# satshakit_fc_power.net
KiCad netlist of a schematic drawn in EAGLE
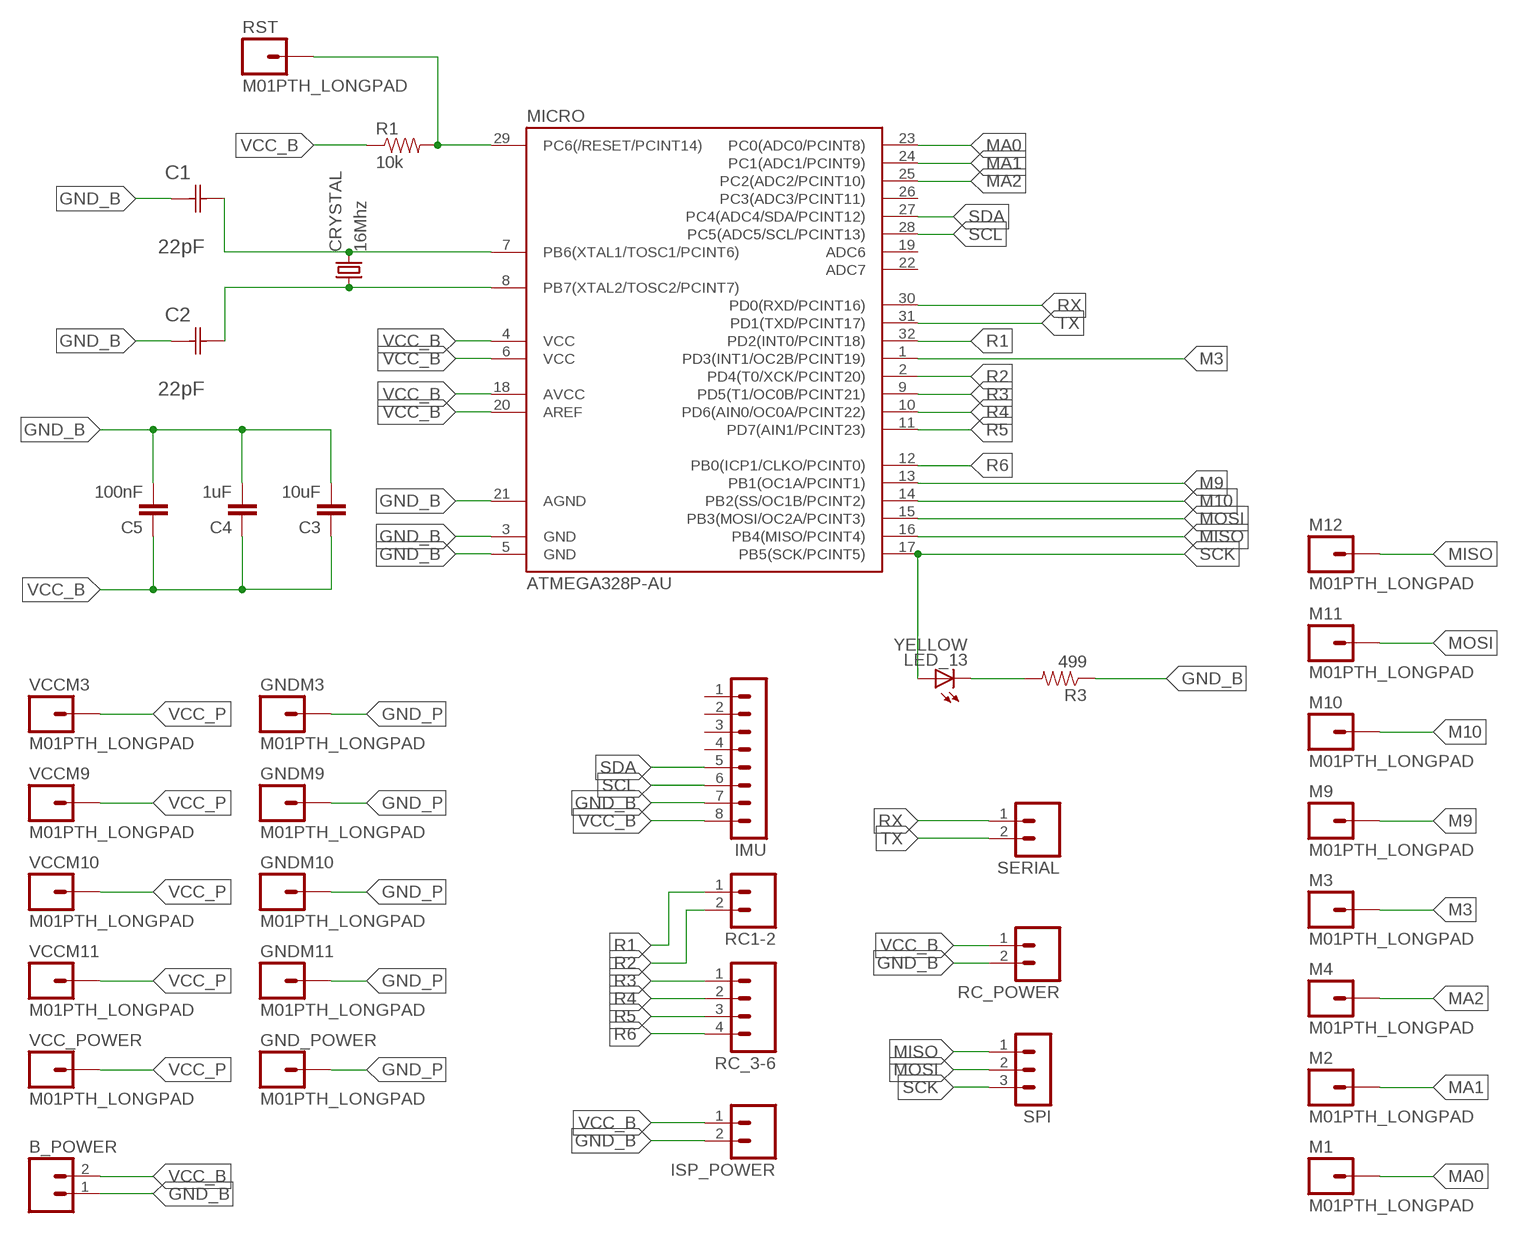
[diagram p0: schematic, sheet 1]

(export (version "E")
  (design (tool "Eeschema 10.0.6"))
  (components
    (comp (ref "B_POWER")
      (value "M02LOCK_LONGPADS")
      (footprint "eagle-import:1X02_LOCK_LONGPADS")
      (libsource (lib "eagle-import") (part "M02LOCK_LONGPADS"))
    )
    (comp (ref "C1")
      (value "22pF")
      (footprint "eagle-import:CAPC3216X178N")
      (fields (field (name "MPN") "0612ZC225MAT2A") (field (name "TOLERANCE") "±20%"))
      (libsource (lib "eagle-import") (part "0612ZC225MAT2A"))
    )
    (comp (ref "C2")
      (value "22pF")
      (footprint "eagle-import:CAPC3216X178N")
      (fields (field (name "MPN") "0612ZC225MAT2A") (field (name "TOLERANCE") "±20%"))
      (libsource (lib "eagle-import") (part "0612ZC225MAT2A"))
    )
    (comp (ref "C3")
      (value "10uF")
      (footprint "eagle-import:1206")
      (libsource (lib "eagle-import") (part "CAP1206"))
    )
    (comp (ref "C4")
      (value "1uF")
      (footprint "eagle-import:1206")
      (libsource (lib "eagle-import") (part "CAP1206"))
    )
    (comp (ref "C5")
      (value "100nF")
      (footprint "eagle-import:1206")
      (libsource (lib "eagle-import") (part "CAP1206"))
    )
    (comp (ref "CRYSTAL")
      (value "16Mhz")
      (footprint "eagle-import:CSM-7X-DU")
      (libsource (lib "eagle-import") (part "CSM-7X-DU"))
    )
    (comp (ref "GNDM3")
      (value "M01PTH_LONGPAD")
      (footprint "eagle-import:1X01_LONGPAD")
      (libsource (lib "eagle-import") (part "M01PTH_LONGPAD"))
    )
    (comp (ref "GNDM9")
      (value "M01PTH_LONGPAD")
      (footprint "eagle-import:1X01_LONGPAD")
      (libsource (lib "eagle-import") (part "M01PTH_LONGPAD"))
    )
    (comp (ref "GNDM10")
      (value "M01PTH_LONGPAD")
      (footprint "eagle-import:1X01_LONGPAD")
      (libsource (lib "eagle-import") (part "M01PTH_LONGPAD"))
    )
    (comp (ref "GNDM11")
      (value "M01PTH_LONGPAD")
      (footprint "eagle-import:1X01_LONGPAD")
      (libsource (lib "eagle-import") (part "M01PTH_LONGPAD"))
    )
    (comp (ref "GND_POWER")
      (value "M01PTH_LONGPAD")
      (footprint "eagle-import:1X01_LONGPAD")
      (libsource (lib "eagle-import") (part "M01PTH_LONGPAD"))
    )
    (comp (ref "IMU")
      (value "MA08-1")
      (footprint "eagle-import:MA08-1")
      (libsource (lib "eagle-import") (part "MA08-1"))
    )
    (comp (ref "ISP_POWER")
      (value "M02LOCK_LONGPADS")
      (footprint "eagle-import:1X02_LOCK_LONGPADS")
      (libsource (lib "eagle-import") (part "M02LOCK_LONGPADS"))
    )
    (comp (ref "LED_13")
      (value "YELLOW")
      (footprint "eagle-import:1206")
      (libsource (lib "eagle-import") (part "LED1206"))
    )
    (comp (ref "M1")
      (value "M01PTH_LONGPAD")
      (footprint "eagle-import:1X01_LONGPAD")
      (libsource (lib "eagle-import") (part "M01PTH_LONGPAD"))
    )
    (comp (ref "M2")
      (value "M01PTH_LONGPAD")
      (footprint "eagle-import:1X01_LONGPAD")
      (libsource (lib "eagle-import") (part "M01PTH_LONGPAD"))
    )
    (comp (ref "M3")
      (value "M01PTH_LONGPAD")
      (footprint "eagle-import:1X01_LONGPAD")
      (libsource (lib "eagle-import") (part "M01PTH_LONGPAD"))
    )
    (comp (ref "M4")
      (value "M01PTH_LONGPAD")
      (footprint "eagle-import:1X01_LONGPAD")
      (libsource (lib "eagle-import") (part "M01PTH_LONGPAD"))
    )
    (comp (ref "M9")
      (value "M01PTH_LONGPAD")
      (footprint "eagle-import:1X01_LONGPAD")
      (libsource (lib "eagle-import") (part "M01PTH_LONGPAD"))
    )
    (comp (ref "M10")
      (value "M01PTH_LONGPAD")
      (footprint "eagle-import:1X01_LONGPAD")
      (libsource (lib "eagle-import") (part "M01PTH_LONGPAD"))
    )
    (comp (ref "M11")
      (value "M01PTH_LONGPAD")
      (footprint "eagle-import:1X01_LONGPAD")
      (libsource (lib "eagle-import") (part "M01PTH_LONGPAD"))
    )
    (comp (ref "M12")
      (value "M01PTH_LONGPAD")
      (footprint "eagle-import:1X01_LONGPAD")
      (libsource (lib "eagle-import") (part "M01PTH_LONGPAD"))
    )
    (comp (ref "MICRO")
      (value "ATMEGA328P-AU")
      (footprint "eagle-import:TQFP32-08")
      (libsource (lib "eagle-import") (part "ATMEGA48/88/168-AU"))
    )
    (comp (ref "R1")
      (value "10k")
      (footprint "eagle-import:1206")
      (libsource (lib "eagle-import") (part "RESISTOR1206"))
    )
    (comp (ref "R3")
      (value "499")
      (footprint "eagle-import:1206")
      (libsource (lib "eagle-import") (part "RESISTOR1206"))
    )
    (comp (ref "RC1-2")
      (value "M02")
      (footprint "eagle-import:02P")
      (libsource (lib "eagle-import") (part "con-amp-quick_M02"))
    )
    (comp (ref "RC_3-6")
      (value "M04LONGPADS")
      (footprint "eagle-import:1X04_LONGPADS")
      (libsource (lib "eagle-import") (part "M04LONGPADS"))
    )
    (comp (ref "RC_POWER")
      (value "M02LOCK_LONGPADS")
      (footprint "eagle-import:1X02_LOCK_LONGPADS")
      (libsource (lib "eagle-import") (part "M02LOCK_LONGPADS"))
    )
    (comp (ref "RST")
      (value "M01PTH_LONGPAD")
      (footprint "eagle-import:1X01_LONGPAD")
      (libsource (lib "eagle-import") (part "M01PTH_LONGPAD"))
    )
    (comp (ref "SERIAL")
      (value "M02LOCK_LONGPADS")
      (footprint "eagle-import:1X02_LOCK_LONGPADS")
      (libsource (lib "eagle-import") (part "M02LOCK_LONGPADS"))
    )
    (comp (ref "SPI")
      (value "MA03-1")
      (footprint "eagle-import:MA03-1")
      (libsource (lib "eagle-import") (part "MA03-1"))
    )
    (comp (ref "VCCM3")
      (value "M01PTH_LONGPAD")
      (footprint "eagle-import:1X01_LONGPAD")
      (libsource (lib "eagle-import") (part "M01PTH_LONGPAD"))
    )
    (comp (ref "VCCM9")
      (value "M01PTH_LONGPAD")
      (footprint "eagle-import:1X01_LONGPAD")
      (libsource (lib "eagle-import") (part "M01PTH_LONGPAD"))
    )
    (comp (ref "VCCM10")
      (value "M01PTH_LONGPAD")
      (footprint "eagle-import:1X01_LONGPAD")
      (libsource (lib "eagle-import") (part "M01PTH_LONGPAD"))
    )
    (comp (ref "VCCM11")
      (value "M01PTH_LONGPAD")
      (footprint "eagle-import:1X01_LONGPAD")
      (libsource (lib "eagle-import") (part "M01PTH_LONGPAD"))
    )
    (comp (ref "VCC_POWER")
      (value "M01PTH_LONGPAD")
      (footprint "eagle-import:1X01_LONGPAD")
      (libsource (lib "eagle-import") (part "M01PTH_LONGPAD"))
    )
  )
  (nets
    (net (code "1") (name "GND_B") (class "Default")
      (node (ref "B_POWER") (pin "1") (pinfunction "1_1") (pintype "passive"))
      (node (ref "C1") (pin "1") (pinfunction "C1_1") (pintype "passive"))
      (node (ref "C2") (pin "1") (pinfunction "C1_1") (pintype "passive"))
      (node (ref "C3") (pin "2") (pinfunction "2_2") (pintype "passive"))
      (node (ref "C4") (pin "2") (pinfunction "2_2") (pintype "passive"))
      (node (ref "C5") (pin "2") (pinfunction "2_2") (pintype "passive"))
      (node (ref "IMU") (pin "7") (pinfunction "7_7") (pintype "passive"))
      (node (ref "ISP_POWER") (pin "2") (pinfunction "2_2") (pintype "passive"))
      (node (ref "MICRO") (pin "21") (pinfunction "AGND_21") (pintype "power_in"))
      (node (ref "MICRO") (pin "3") (pinfunction "GND_3") (pintype "power_in"))
      (node (ref "MICRO") (pin "5") (pinfunction "GND_5") (pintype "power_in"))
      (node (ref "R3") (pin "1") (pinfunction "1_1") (pintype "passive"))
      (node (ref "RC_POWER") (pin "2") (pinfunction "2_2") (pintype "passive"))
    )
    (net (code "2") (name "GND_P") (class "Default")
      (node (ref "GNDM10") (pin "1") (pinfunction "1_1") (pintype "passive"))
      (node (ref "GNDM11") (pin "1") (pinfunction "1_1") (pintype "passive"))
      (node (ref "GNDM3") (pin "1") (pinfunction "1_1") (pintype "passive"))
      (node (ref "GNDM9") (pin "1") (pinfunction "1_1") (pintype "passive"))
      (node (ref "GND_POWER") (pin "1") (pinfunction "1_1") (pintype "passive"))
    )
    (net (code "3") (name "M3") (class "Default")
      (node (ref "M3") (pin "1") (pinfunction "1_1") (pintype "passive"))
      (node (ref "MICRO") (pin "1") (pinfunction "PD3(INT1/OC2B/PCINT19)_1") (pintype "bidirectional"))
    )
    (net (code "4") (name "M9") (class "Default")
      (node (ref "M9") (pin "1") (pinfunction "1_1") (pintype "passive"))
      (node (ref "MICRO") (pin "13") (pinfunction "PB1(OC1A/PCINT1)_13") (pintype "bidirectional"))
    )
    (net (code "5") (name "M10") (class "Default")
      (node (ref "M10") (pin "1") (pinfunction "1_1") (pintype "passive"))
      (node (ref "MICRO") (pin "14") (pinfunction "PB2(SS/OC1B/PCINT2)_14") (pintype "bidirectional"))
    )
    (net (code "6") (name "MA0") (class "Default")
      (node (ref "M1") (pin "1") (pinfunction "1_1") (pintype "passive"))
      (node (ref "MICRO") (pin "23") (pinfunction "PC0(ADC0/PCINT8)_23") (pintype "bidirectional"))
    )
    (net (code "7") (name "MA1") (class "Default")
      (node (ref "M2") (pin "1") (pinfunction "1_1") (pintype "passive"))
      (node (ref "MICRO") (pin "24") (pinfunction "PC1(ADC1/PCINT9)_24") (pintype "bidirectional"))
    )
    (net (code "8") (name "MA2") (class "Default")
      (node (ref "M4") (pin "1") (pinfunction "1_1") (pintype "passive"))
      (node (ref "MICRO") (pin "25") (pinfunction "PC2(ADC2/PCINT10)_25") (pintype "bidirectional"))
    )
    (net (code "9") (name "MISO") (class "Default")
      (node (ref "M12") (pin "1") (pinfunction "1_1") (pintype "passive"))
      (node (ref "MICRO") (pin "16") (pinfunction "PB4(MISO/PCINT4)_16") (pintype "bidirectional"))
      (node (ref "SPI") (pin "1") (pinfunction "1_1") (pintype "passive"))
    )
    (net (code "10") (name "MOSI") (class "Default")
      (node (ref "M11") (pin "1") (pinfunction "1_1") (pintype "passive"))
      (node (ref "MICRO") (pin "15") (pinfunction "PB3(MOSI/OC2A/PCINT3)_15") (pintype "bidirectional"))
      (node (ref "SPI") (pin "2") (pinfunction "2_2") (pintype "passive"))
    )
    (net (code "11") (name "Net-(C1-C2)") (class "Default")
      (node (ref "C1") (pin "2") (pinfunction "C2_2") (pintype "passive"))
      (node (ref "CRYSTAL") (pin "2") (pinfunction "2_2") (pintype "passive"))
      (node (ref "MICRO") (pin "7") (pinfunction "PB6(XTAL1/TOSC1/PCINT6)_7") (pintype "bidirectional"))
    )
    (net (code "12") (name "Net-(C2-C2)") (class "Default")
      (node (ref "C2") (pin "2") (pinfunction "C2_2") (pintype "passive"))
      (node (ref "CRYSTAL") (pin "1") (pinfunction "1_1") (pintype "passive"))
      (node (ref "MICRO") (pin "8") (pinfunction "PB7(XTAL2/TOSC2/PCINT7)_8") (pintype "bidirectional"))
    )
    (net (code "13") (name "Net-(LED_13-C)") (class "Default")
      (node (ref "LED_13") (pin "2") (pinfunction "C_2") (pintype "passive"))
      (node (ref "R3") (pin "2") (pinfunction "2_2") (pintype "passive"))
    )
    (net (code "14") (name "Net-(MICRO-PC6({slash}RESET{slash}PCINT14))") (class "Default")
      (node (ref "MICRO") (pin "29") (pinfunction "PC6(/RESET/PCINT14)_29") (pintype "bidirectional"))
      (node (ref "R1") (pin "2") (pinfunction "2_2") (pintype "passive"))
      (node (ref "RST") (pin "1") (pinfunction "1_1") (pintype "passive"))
    )
    (net (code "15") (name "R1") (class "Default")
      (node (ref "MICRO") (pin "32") (pinfunction "PD2(INT0/PCINT18)_32") (pintype "bidirectional"))
      (node (ref "RC1-2") (pin "1") (pinfunction "1_1") (pintype "passive"))
    )
    (net (code "16") (name "R2") (class "Default")
      (node (ref "MICRO") (pin "2") (pinfunction "PD4(T0/XCK/PCINT20)_2") (pintype "bidirectional"))
      (node (ref "RC1-2") (pin "2") (pinfunction "2_2") (pintype "passive"))
    )
    (net (code "17") (name "R3") (class "Default")
      (node (ref "MICRO") (pin "9") (pinfunction "PD5(T1/OC0B/PCINT21)_9") (pintype "bidirectional"))
      (node (ref "RC_3-6") (pin "1") (pinfunction "1_1") (pintype "passive"))
    )
    (net (code "18") (name "R4") (class "Default")
      (node (ref "MICRO") (pin "10") (pinfunction "PD6(AIN0/OC0A/PCINT22)_10") (pintype "bidirectional"))
      (node (ref "RC_3-6") (pin "2") (pinfunction "2_2") (pintype "passive"))
    )
    (net (code "19") (name "R5") (class "Default")
      (node (ref "MICRO") (pin "11") (pinfunction "PD7(AIN1/PCINT23)_11") (pintype "bidirectional"))
      (node (ref "RC_3-6") (pin "3") (pinfunction "3_3") (pintype "passive"))
    )
    (net (code "20") (name "R6") (class "Default")
      (node (ref "MICRO") (pin "12") (pinfunction "PB0(ICP1/CLKO/PCINT0)_12") (pintype "bidirectional"))
      (node (ref "RC_3-6") (pin "4") (pinfunction "4_4") (pintype "passive"))
    )
    (net (code "21") (name "RX") (class "Default")
      (node (ref "MICRO") (pin "30") (pinfunction "PD0(RXD/PCINT16)_30") (pintype "bidirectional"))
      (node (ref "SERIAL") (pin "1") (pinfunction "1_1") (pintype "passive"))
    )
    (net (code "22") (name "SCK") (class "Default")
      (node (ref "LED_13") (pin "1") (pinfunction "A_1") (pintype "passive"))
      (node (ref "MICRO") (pin "17") (pinfunction "PB5(SCK/PCINT5)_17") (pintype "bidirectional"))
      (node (ref "SPI") (pin "3") (pinfunction "3_3") (pintype "passive"))
    )
    (net (code "23") (name "SCL") (class "Default")
      (node (ref "IMU") (pin "6") (pinfunction "6_6") (pintype "passive"))
      (node (ref "MICRO") (pin "28") (pinfunction "PC5(ADC5/SCL/PCINT13)_28") (pintype "bidirectional"))
    )
    (net (code "24") (name "SDA") (class "Default")
      (node (ref "IMU") (pin "5") (pinfunction "5_5") (pintype "passive"))
      (node (ref "MICRO") (pin "27") (pinfunction "PC4(ADC4/SDA/PCINT12)_27") (pintype "bidirectional"))
    )
    (net (code "25") (name "TX") (class "Default")
      (node (ref "MICRO") (pin "31") (pinfunction "PD1(TXD/PCINT17)_31") (pintype "bidirectional"))
      (node (ref "SERIAL") (pin "2") (pinfunction "2_2") (pintype "passive"))
    )
    (net (code "26") (name "VCC_B") (class "Default")
      (node (ref "B_POWER") (pin "2") (pinfunction "2_2") (pintype "passive"))
      (node (ref "C3") (pin "1") (pinfunction "1_1") (pintype "passive"))
      (node (ref "C4") (pin "1") (pinfunction "1_1") (pintype "passive"))
      (node (ref "C5") (pin "1") (pinfunction "1_1") (pintype "passive"))
      (node (ref "IMU") (pin "8") (pinfunction "8_8") (pintype "passive"))
      (node (ref "ISP_POWER") (pin "1") (pinfunction "1_1") (pintype "passive"))
      (node (ref "MICRO") (pin "18") (pinfunction "AVCC_18") (pintype "passive"))
      (node (ref "MICRO") (pin "20") (pinfunction "AREF_20") (pintype "passive"))
      (node (ref "MICRO") (pin "4") (pinfunction "VCC_4") (pintype "power_in"))
      (node (ref "MICRO") (pin "6") (pinfunction "VCC_6") (pintype "power_in"))
      (node (ref "R1") (pin "1") (pinfunction "1_1") (pintype "passive"))
      (node (ref "RC_POWER") (pin "1") (pinfunction "1_1") (pintype "passive"))
    )
    (net (code "27") (name "VCC_P") (class "Default")
      (node (ref "VCCM10") (pin "1") (pinfunction "1_1") (pintype "passive"))
      (node (ref "VCCM11") (pin "1") (pinfunction "1_1") (pintype "passive"))
      (node (ref "VCCM3") (pin "1") (pinfunction "1_1") (pintype "passive"))
      (node (ref "VCCM9") (pin "1") (pinfunction "1_1") (pintype "passive"))
      (node (ref "VCC_POWER") (pin "1") (pinfunction "1_1") (pintype "passive"))
    )
    (net (code "28") (name "unconnected-(IMU-Pad1)") (class "Default")
      (node (ref "IMU") (pin "1") (pinfunction "1_1") (pintype "passive"))
    )
    (net (code "29") (name "unconnected-(IMU-Pad2)") (class "Default")
      (node (ref "IMU") (pin "2") (pinfunction "2_2") (pintype "passive"))
    )
    (net (code "30") (name "unconnected-(IMU-Pad3)") (class "Default")
      (node (ref "IMU") (pin "3") (pinfunction "3_3") (pintype "passive"))
    )
    (net (code "31") (name "unconnected-(IMU-Pad4)") (class "Default")
      (node (ref "IMU") (pin "4") (pinfunction "4_4") (pintype "passive"))
    )
    (net (code "32") (name "unconnected-(MICRO-ADC6-Pad19)") (class "Default")
      (node (ref "MICRO") (pin "19") (pinfunction "ADC6_19") (pintype "passive"))
    )
    (net (code "33") (name "unconnected-(MICRO-ADC7-Pad22)") (class "Default")
      (node (ref "MICRO") (pin "22") (pinfunction "ADC7_22") (pintype "passive"))
    )
    (net (code "34") (name "unconnected-(MICRO-PC3(ADC3{slash}PCINT11)-Pad26)") (class "Default")
      (node (ref "MICRO") (pin "26") (pinfunction "PC3(ADC3/PCINT11)_26") (pintype "bidirectional"))
    )
  )
)
